# utilidong-soc-mk-1_0.net
KiCad netlist of a schematic drawn in EAGLE
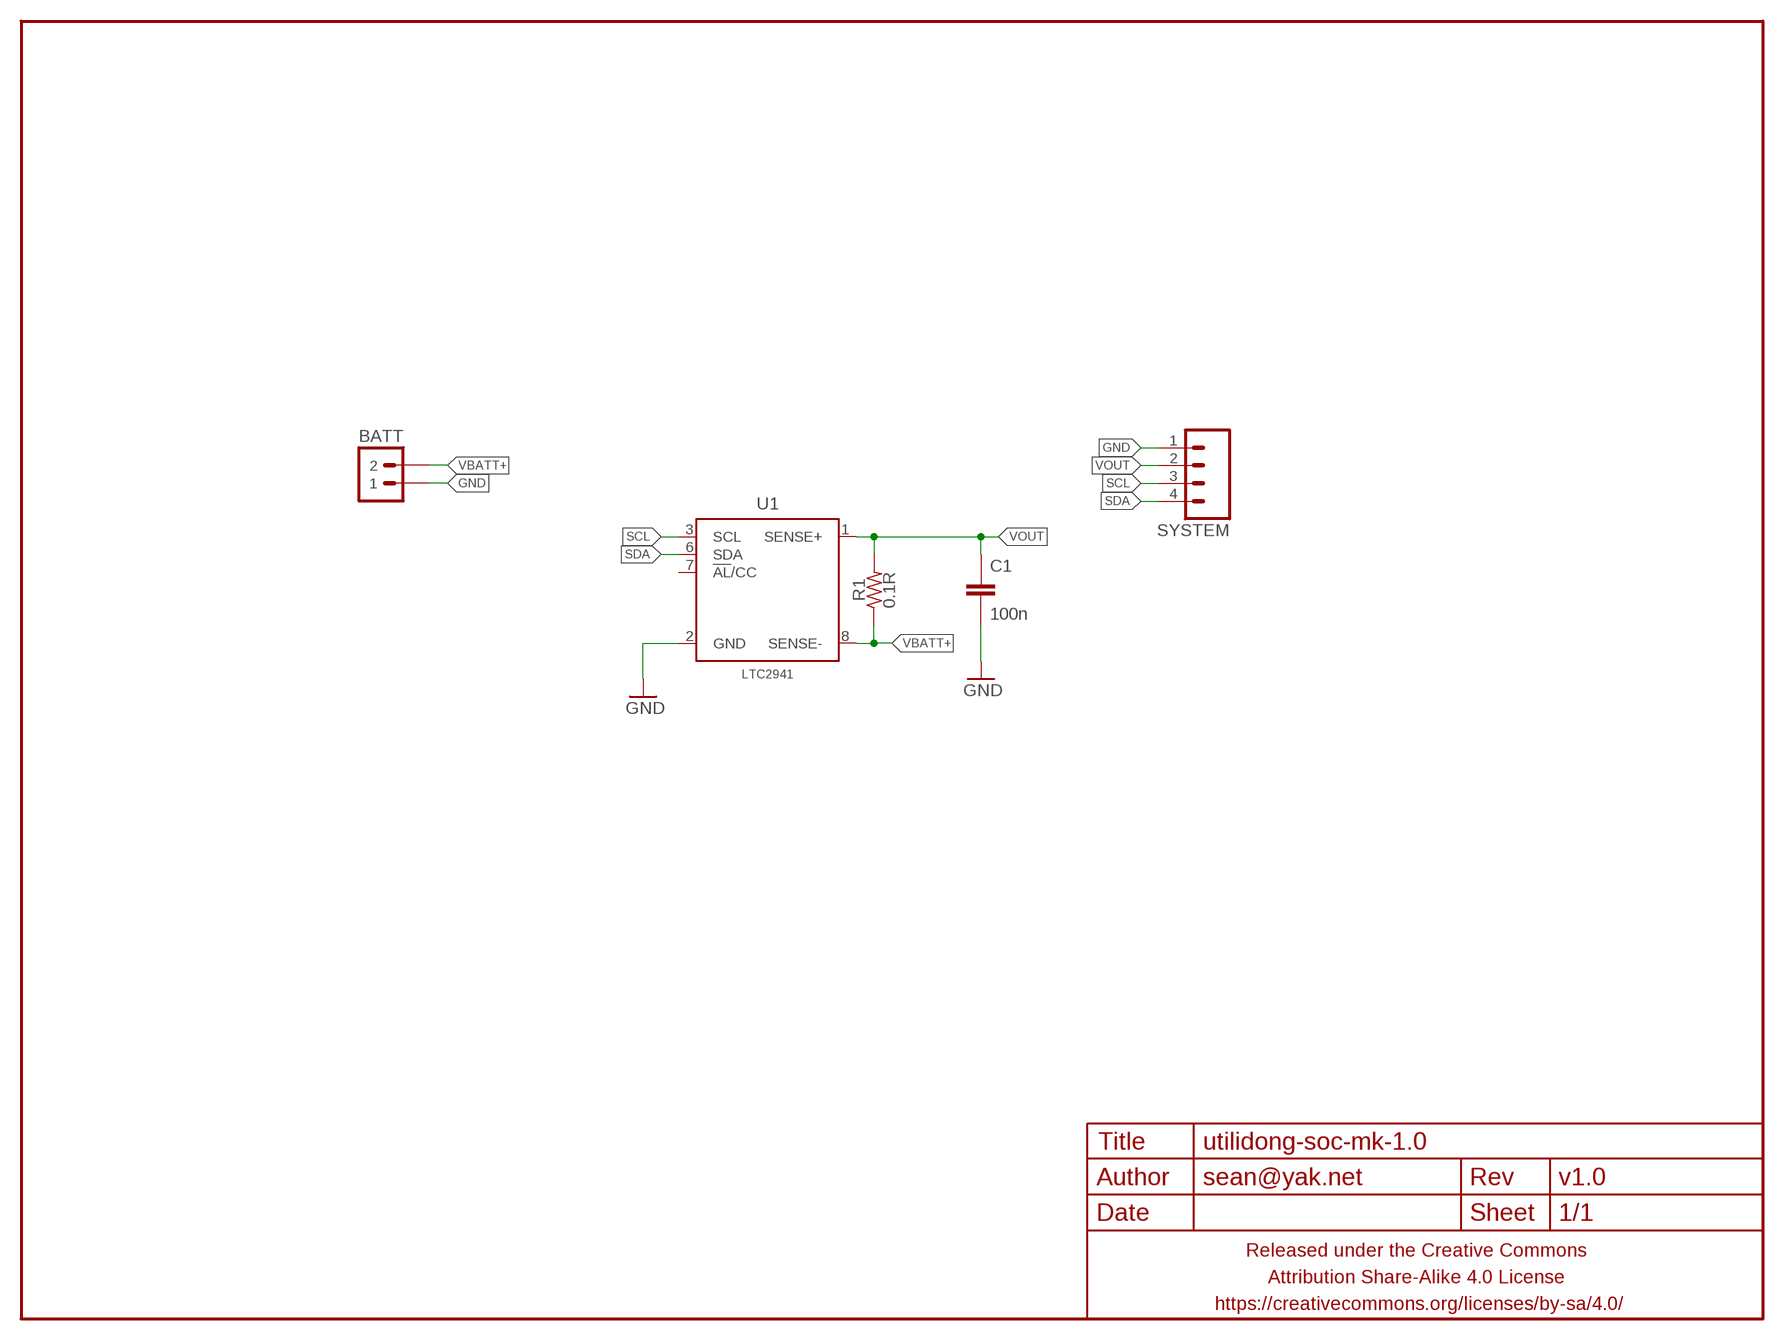
[diagram p0: schematic, sheet 1]

(export (version "E")
  (design (tool "Eeschema 10.0.6"))
  (components
    (comp (ref "BATT")
      (value "M02PTH-CENTERED-R+")
      (footprint "eagle-import:1X02-CENTER-R+")
      (libsource (lib "eagle-import") (part "M02PTH-CENTERED-R+"))
    )
    (comp (ref "C1")
      (value "100n")
      (footprint "eagle-import:C0603")
      (libsource (lib "eagle-import") (part "CAPACITOR-CERAMICC0603"))
    )
    (comp (ref "FRAME1")
      (value "FRAME-LETTERNO_PACKAGE")
      (footprint "eagle-import:DUMMY")
      (fields (field (name "DESIGNER") "sean@yak.net") (field (name "VERSION") "v1.0"))
      (libsource (lib "eagle-import") (part "FRAME-LETTERNO_PACKAGE"))
    )
    (comp (ref "R1")
      (value "0.1R")
      (footprint "eagle-import:R1206")
      (libsource (lib "eagle-import") (part "RESISTORR1206"))
    )
    (comp (ref "SYSTEM")
      (value "M04PTH-CENTERED")
      (footprint "eagle-import:1X04-PTH-VERT-CENTER")
      (libsource (lib "eagle-import") (part "M04PTH-CENTERED"))
    )
    (comp (ref "U1")
      (value "LTC2941")
      (footprint "eagle-import:MSOP-8")
      (libsource (lib "eagle-import") (part "LTC2941MSOP-8"))
    )
  )
  (nets
    (net (code "1") (name "GND") (class "Default")
      (node (ref "BATT") (pin "1") (pinfunction "1_1") (pintype "passive"))
      (node (ref "C1") (pin "2") (pinfunction "2_2") (pintype "passive"))
      (node (ref "SYSTEM") (pin "1") (pinfunction "1_1") (pintype "passive"))
      (node (ref "U1") (pin "2") (pinfunction "GND_2") (pintype "bidirectional"))
    )
    (net (code "2") (name "SCL") (class "Default")
      (node (ref "SYSTEM") (pin "3") (pinfunction "3_3") (pintype "passive"))
      (node (ref "U1") (pin "3") (pinfunction "SCL_3") (pintype "bidirectional"))
    )
    (net (code "3") (name "SDA") (class "Default")
      (node (ref "SYSTEM") (pin "4") (pinfunction "4_4") (pintype "passive"))
      (node (ref "U1") (pin "6") (pinfunction "SDA_6") (pintype "bidirectional"))
    )
    (net (code "4") (name "VBATT+") (class "Default")
      (node (ref "BATT") (pin "2") (pinfunction "2_2") (pintype "passive"))
      (node (ref "R1") (pin "1") (pinfunction "1_1") (pintype "passive"))
      (node (ref "U1") (pin "8") (pinfunction "SENSE-_8") (pintype "bidirectional"))
    )
    (net (code "5") (name "VOUT") (class "Default")
      (node (ref "C1") (pin "1") (pinfunction "1_1") (pintype "passive"))
      (node (ref "R1") (pin "2") (pinfunction "2_2") (pintype "passive"))
      (node (ref "SYSTEM") (pin "2") (pinfunction "2_2") (pintype "passive"))
      (node (ref "U1") (pin "1") (pinfunction "SENSE+_1") (pintype "bidirectional"))
    )
    (net (code "6") (name "unconnected-(U1-~{AL}{slash}CC-Pad7)") (class "Default")
      (node (ref "U1") (pin "7") (pinfunction "~{AL}/CC_7") (pintype "bidirectional"))
    )
  )
)
